# pianotiles.net
KiCad netlist of a schematic drawn in EAGLE
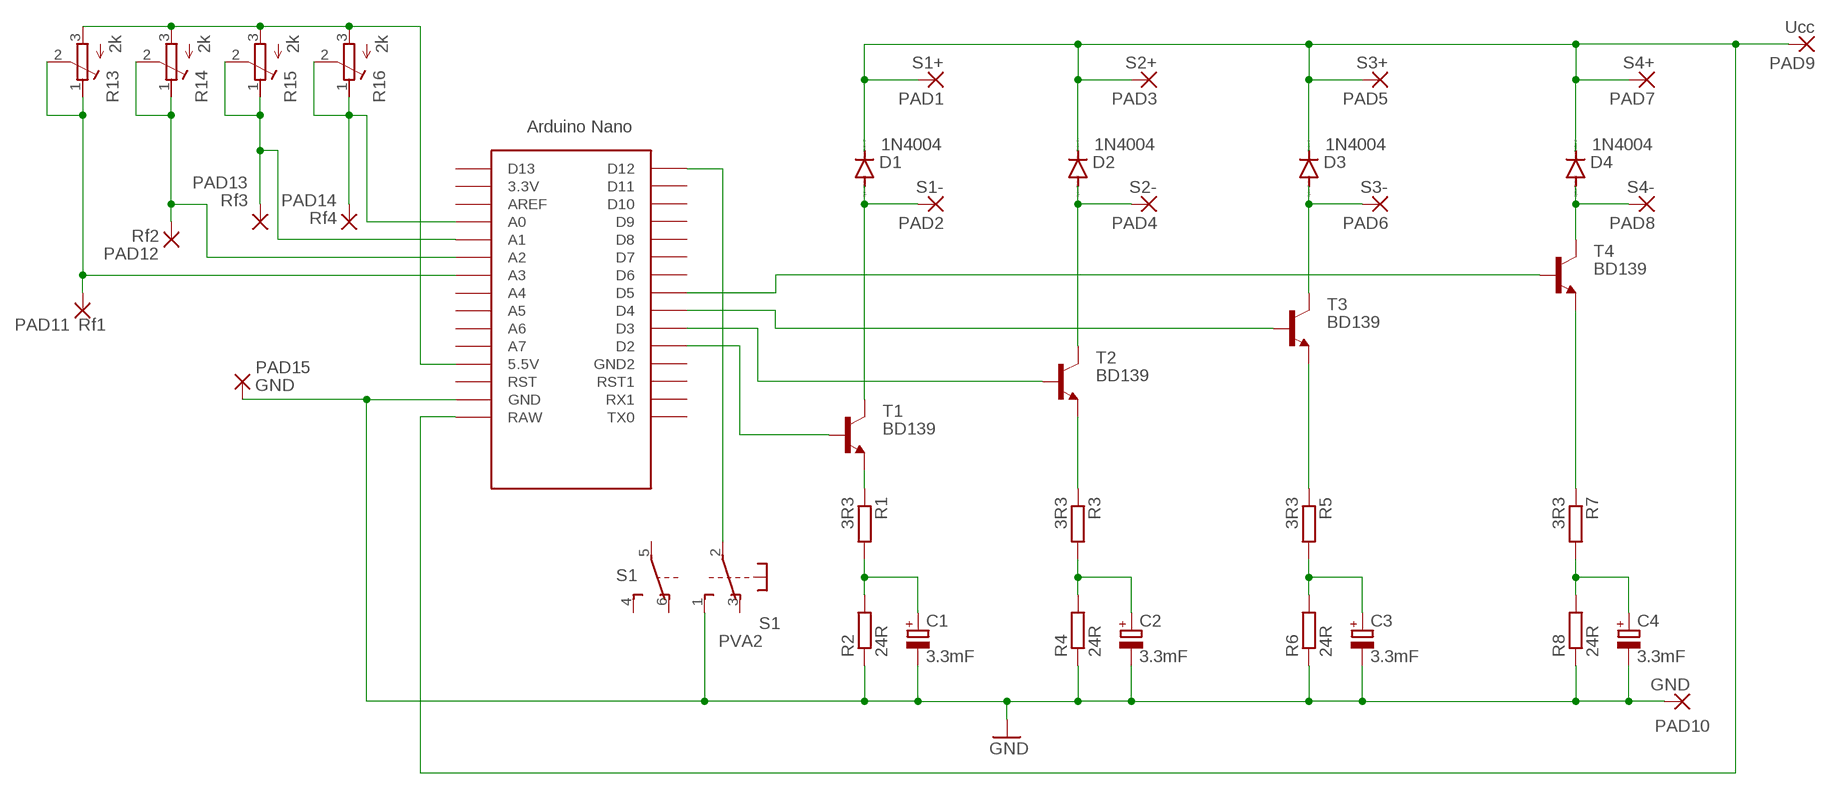
[diagram p0: schematic, sheet 1]

(export (version "E")
  (design (tool "Eeschema 10.0.6"))
  (components
    (comp (ref "C1")
      (value "3.3mF")
      (footprint "eagle-import:E5-10,5")
      (libsource (lib "eagle-import") (part "CPOL-EUE5-10.5"))
    )
    (comp (ref "C2")
      (value "3.3mF")
      (footprint "eagle-import:E5-10,5")
      (libsource (lib "eagle-import") (part "CPOL-EUE5-10.5"))
    )
    (comp (ref "C3")
      (value "3.3mF")
      (footprint "eagle-import:E5-10,5")
      (libsource (lib "eagle-import") (part "CPOL-EUE5-10.5"))
    )
    (comp (ref "C4")
      (value "3.3mF")
      (footprint "eagle-import:E5-10,5")
      (libsource (lib "eagle-import") (part "CPOL-EUE5-10.5"))
    )
    (comp (ref "D1")
      (value "1N4004")
      (footprint "eagle-import:DO41-10")
      (libsource (lib "eagle-import") (part "1N4004"))
    )
    (comp (ref "D2")
      (value "1N4004")
      (footprint "eagle-import:DO41-10")
      (libsource (lib "eagle-import") (part "1N4004"))
    )
    (comp (ref "D3")
      (value "1N4004")
      (footprint "eagle-import:DO41-10")
      (libsource (lib "eagle-import") (part "1N4004"))
    )
    (comp (ref "D4")
      (value "1N4004")
      (footprint "eagle-import:DO41-10")
      (libsource (lib "eagle-import") (part "1N4004"))
    )
    (comp (ref "PAD1")
      (value "S1+")
      (footprint "eagle-import:2,15_1,0")
      (libsource (lib "eagle-import") (part "2,15/1,0"))
    )
    (comp (ref "PAD2")
      (value "S1-")
      (footprint "eagle-import:2,15_1,0")
      (libsource (lib "eagle-import") (part "2,15/1,0"))
    )
    (comp (ref "PAD3")
      (value "S2+")
      (footprint "eagle-import:2,15_1,0")
      (libsource (lib "eagle-import") (part "2,15/1,0"))
    )
    (comp (ref "PAD4")
      (value "S2-")
      (footprint "eagle-import:2,15_1,0")
      (libsource (lib "eagle-import") (part "2,15/1,0"))
    )
    (comp (ref "PAD5")
      (value "S3+")
      (footprint "eagle-import:2,15_1,0")
      (libsource (lib "eagle-import") (part "2,15/1,0"))
    )
    (comp (ref "PAD6")
      (value "S3-")
      (footprint "eagle-import:2,15_1,0")
      (libsource (lib "eagle-import") (part "2,15/1,0"))
    )
    (comp (ref "PAD7")
      (value "S4+")
      (footprint "eagle-import:2,15_1,0")
      (libsource (lib "eagle-import") (part "2,15/1,0"))
    )
    (comp (ref "PAD8")
      (value "S4-")
      (footprint "eagle-import:2,15_1,0")
      (libsource (lib "eagle-import") (part "2,15/1,0"))
    )
    (comp (ref "PAD9")
      (value "Ucc")
      (footprint "eagle-import:2,54_1,0")
      (libsource (lib "eagle-import") (part "2,54/1,0"))
    )
    (comp (ref "PAD10")
      (value "GND")
      (footprint "eagle-import:2,54_1,0")
      (libsource (lib "eagle-import") (part "2,54/1,0"))
    )
    (comp (ref "PAD11")
      (value "Rf1")
      (footprint "eagle-import:2,15_1,0")
      (libsource (lib "eagle-import") (part "2,15/1,0"))
    )
    (comp (ref "PAD12")
      (value "Rf2")
      (footprint "eagle-import:2,15_1,0")
      (libsource (lib "eagle-import") (part "2,15/1,0"))
    )
    (comp (ref "PAD13")
      (value "Rf3")
      (footprint "eagle-import:2,15_1,0")
      (libsource (lib "eagle-import") (part "2,15/1,0"))
    )
    (comp (ref "PAD14")
      (value "Rf4")
      (footprint "eagle-import:2,15_1,0")
      (libsource (lib "eagle-import") (part "2,15/1,0"))
    )
    (comp (ref "PAD15")
      (value "GND")
      (footprint "eagle-import:2,15_1,0")
      (libsource (lib "eagle-import") (part "2,15/1,0"))
    )
    (comp (ref "R1")
      (value "3R3")
      (footprint "eagle-import:0309_10")
      (libsource (lib "eagle-import") (part "R-EU_0309/10"))
    )
    (comp (ref "R2")
      (value "24R")
      (footprint "eagle-import:0309_10")
      (libsource (lib "eagle-import") (part "R-EU_0309/10"))
    )
    (comp (ref "R3")
      (value "3R3")
      (footprint "eagle-import:0309_10")
      (libsource (lib "eagle-import") (part "R-EU_0309/10"))
    )
    (comp (ref "R4")
      (value "24R")
      (footprint "eagle-import:0309_10")
      (libsource (lib "eagle-import") (part "R-EU_0309/10"))
    )
    (comp (ref "R5")
      (value "3R3")
      (footprint "eagle-import:0309_10")
      (libsource (lib "eagle-import") (part "R-EU_0309/10"))
    )
    (comp (ref "R6")
      (value "24R")
      (footprint "eagle-import:0309_10")
      (libsource (lib "eagle-import") (part "R-EU_0309/10"))
    )
    (comp (ref "R7")
      (value "3R3")
      (footprint "eagle-import:0309_10")
      (libsource (lib "eagle-import") (part "R-EU_0309/10"))
    )
    (comp (ref "R8")
      (value "24R")
      (footprint "eagle-import:0309_10")
      (libsource (lib "eagle-import") (part "R-EU_0309/10"))
    )
    (comp (ref "R13")
      (value "2k")
      (footprint "eagle-import:RTRIMT93YA")
      (libsource (lib "eagle-import") (part "R-TRIMMT93YA"))
    )
    (comp (ref "R14")
      (value "2k")
      (footprint "eagle-import:RTRIMT93YA")
      (libsource (lib "eagle-import") (part "R-TRIMMT93YA"))
    )
    (comp (ref "R15")
      (value "2k")
      (footprint "eagle-import:RTRIMT93YA")
      (libsource (lib "eagle-import") (part "R-TRIMMT93YA"))
    )
    (comp (ref "R16")
      (value "2k")
      (footprint "eagle-import:RTRIMT93YA")
      (libsource (lib "eagle-import") (part "R-TRIMMT93YA"))
    )
    (comp (ref "S1")
      (value "PVA2")
      (footprint "eagle-import:PVA2F")
      (libsource (lib "eagle-import") (part "PVA2"))
    )
    (comp (ref "T1")
      (value "BD139")
      (footprint "eagle-import:TO126")
      (libsource (lib "eagle-import") (part "BD139"))
    )
    (comp (ref "T2")
      (value "BD139")
      (footprint "eagle-import:TO126")
      (libsource (lib "eagle-import") (part "BD139"))
    )
    (comp (ref "T3")
      (value "BD139")
      (footprint "eagle-import:TO126")
      (libsource (lib "eagle-import") (part "BD139"))
    )
    (comp (ref "T4")
      (value "BD139")
      (footprint "eagle-import:TO126")
      (libsource (lib "eagle-import") (part "BD139"))
    )
    (comp (ref "U$1")
      (value "NANO")
      (footprint "eagle-import:NANO")
      (libsource (lib "eagle-import") (part "NANO"))
    )
  )
  (nets
    (net (code "1") (name "GND") (class "Default")
      (node (ref "C1") (pin "-") (pinfunction "-_-") (pintype "passive"))
      (node (ref "C2") (pin "-") (pinfunction "-_-") (pintype "passive"))
      (node (ref "C3") (pin "-") (pinfunction "-_-") (pintype "passive"))
      (node (ref "C4") (pin "-") (pinfunction "-_-") (pintype "passive"))
      (node (ref "PAD10") (pin "1") (pinfunction "P_1") (pintype "passive"))
      (node (ref "PAD15") (pin "1") (pinfunction "P_1") (pintype "passive"))
      (node (ref "R2") (pin "1") (pinfunction "1_1") (pintype "passive"))
      (node (ref "R4") (pin "1") (pinfunction "1_1") (pintype "passive"))
      (node (ref "R6") (pin "1") (pinfunction "1_1") (pintype "passive"))
      (node (ref "R8") (pin "1") (pinfunction "1_1") (pintype "passive"))
      (node (ref "S1") (pin "1") (pinfunction "S_1") (pintype "passive"))
      (node (ref "U$1") (pin "GND") (pinfunction "GND_GND") (pintype "bidirectional"))
    )
    (net (code "2") (name "Net-(C1-Pad+)") (class "Default")
      (node (ref "C1") (pin "+") (pinfunction "+_+") (pintype "passive"))
      (node (ref "R1") (pin "2") (pinfunction "2_2") (pintype "passive"))
      (node (ref "R2") (pin "2") (pinfunction "2_2") (pintype "passive"))
    )
    (net (code "3") (name "Net-(C2-Pad+)") (class "Default")
      (node (ref "C2") (pin "+") (pinfunction "+_+") (pintype "passive"))
      (node (ref "R3") (pin "2") (pinfunction "2_2") (pintype "passive"))
      (node (ref "R4") (pin "2") (pinfunction "2_2") (pintype "passive"))
    )
    (net (code "4") (name "Net-(C3-Pad+)") (class "Default")
      (node (ref "C3") (pin "+") (pinfunction "+_+") (pintype "passive"))
      (node (ref "R5") (pin "2") (pinfunction "2_2") (pintype "passive"))
      (node (ref "R6") (pin "2") (pinfunction "2_2") (pintype "passive"))
    )
    (net (code "5") (name "Net-(C4-Pad+)") (class "Default")
      (node (ref "C4") (pin "+") (pinfunction "+_+") (pintype "passive"))
      (node (ref "R7") (pin "2") (pinfunction "2_2") (pintype "passive"))
      (node (ref "R8") (pin "2") (pinfunction "2_2") (pintype "passive"))
    )
    (net (code "6") (name "Net-(PAD1-P)") (class "Default")
      (node (ref "D1") (pin "C") (pinfunction "C_C") (pintype "passive"))
      (node (ref "D2") (pin "C") (pinfunction "C_C") (pintype "passive"))
      (node (ref "D3") (pin "C") (pinfunction "C_C") (pintype "passive"))
      (node (ref "D4") (pin "C") (pinfunction "C_C") (pintype "passive"))
      (node (ref "PAD1") (pin "1") (pinfunction "P_1") (pintype "passive"))
      (node (ref "PAD3") (pin "1") (pinfunction "P_1") (pintype "passive"))
      (node (ref "PAD5") (pin "1") (pinfunction "P_1") (pintype "passive"))
      (node (ref "PAD7") (pin "1") (pinfunction "P_1") (pintype "passive"))
      (node (ref "PAD9") (pin "1") (pinfunction "P_1") (pintype "passive"))
      (node (ref "U$1") (pin "RAW") (pinfunction "RAW_RAW") (pintype "bidirectional"))
    )
    (net (code "7") (name "Net-(PAD2-P)") (class "Default")
      (node (ref "D1") (pin "A") (pinfunction "A_A") (pintype "passive"))
      (node (ref "PAD2") (pin "1") (pinfunction "P_1") (pintype "passive"))
      (node (ref "T1") (pin "2") (pinfunction "C_2") (pintype "passive"))
    )
    (net (code "8") (name "Net-(PAD4-P)") (class "Default")
      (node (ref "D2") (pin "A") (pinfunction "A_A") (pintype "passive"))
      (node (ref "PAD4") (pin "1") (pinfunction "P_1") (pintype "passive"))
      (node (ref "T2") (pin "2") (pinfunction "C_2") (pintype "passive"))
    )
    (net (code "9") (name "Net-(PAD6-P)") (class "Default")
      (node (ref "D3") (pin "A") (pinfunction "A_A") (pintype "passive"))
      (node (ref "PAD6") (pin "1") (pinfunction "P_1") (pintype "passive"))
      (node (ref "T3") (pin "2") (pinfunction "C_2") (pintype "passive"))
    )
    (net (code "10") (name "Net-(PAD8-P)") (class "Default")
      (node (ref "D4") (pin "A") (pinfunction "A_A") (pintype "passive"))
      (node (ref "PAD8") (pin "1") (pinfunction "P_1") (pintype "passive"))
      (node (ref "T4") (pin "2") (pinfunction "C_2") (pintype "passive"))
    )
    (net (code "11") (name "Net-(PAD11-P)") (class "Default")
      (node (ref "PAD11") (pin "1") (pinfunction "P_1") (pintype "passive"))
      (node (ref "R13") (pin "1") (pinfunction "E_1") (pintype "passive"))
      (node (ref "R13") (pin "2") (pinfunction "S_2") (pintype "passive"))
      (node (ref "U$1") (pin "A3") (pinfunction "A3_A3") (pintype "bidirectional"))
    )
    (net (code "12") (name "Net-(PAD12-P)") (class "Default")
      (node (ref "PAD12") (pin "1") (pinfunction "P_1") (pintype "passive"))
      (node (ref "R14") (pin "1") (pinfunction "E_1") (pintype "passive"))
      (node (ref "R14") (pin "2") (pinfunction "S_2") (pintype "passive"))
      (node (ref "U$1") (pin "A2") (pinfunction "A2_A2") (pintype "bidirectional"))
    )
    (net (code "13") (name "Net-(PAD13-P)") (class "Default")
      (node (ref "PAD13") (pin "1") (pinfunction "P_1") (pintype "passive"))
      (node (ref "R15") (pin "1") (pinfunction "E_1") (pintype "passive"))
      (node (ref "R15") (pin "2") (pinfunction "S_2") (pintype "passive"))
      (node (ref "U$1") (pin "A1") (pinfunction "A1_A1") (pintype "bidirectional"))
    )
    (net (code "14") (name "Net-(PAD14-P)") (class "Default")
      (node (ref "PAD14") (pin "1") (pinfunction "P_1") (pintype "passive"))
      (node (ref "R16") (pin "1") (pinfunction "E_1") (pintype "passive"))
      (node (ref "R16") (pin "2") (pinfunction "S_2") (pintype "passive"))
      (node (ref "U$1") (pin "A0") (pinfunction "A0_A0") (pintype "bidirectional"))
    )
    (net (code "15") (name "Net-(R13-A)") (class "Default")
      (node (ref "R13") (pin "3") (pinfunction "A_3") (pintype "passive"))
      (node (ref "R14") (pin "3") (pinfunction "A_3") (pintype "passive"))
      (node (ref "R15") (pin "3") (pinfunction "A_3") (pintype "passive"))
      (node (ref "R16") (pin "3") (pinfunction "A_3") (pintype "passive"))
      (node (ref "U$1") (pin "5V") (pinfunction "5.5V_5V") (pintype "bidirectional"))
    )
    (net (code "16") (name "Net-(S1A-P)") (class "Default")
      (node (ref "S1") (pin "2") (pinfunction "P_2") (pintype "passive"))
      (node (ref "U$1") (pin "D12") (pinfunction "D12_D12") (pintype "bidirectional"))
    )
    (net (code "17") (name "Net-(T1-B)") (class "Default")
      (node (ref "T1") (pin "3") (pinfunction "B_3") (pintype "passive"))
      (node (ref "U$1") (pin "D2") (pinfunction "D2_D2") (pintype "bidirectional"))
    )
    (net (code "18") (name "Net-(T1-E)") (class "Default")
      (node (ref "R1") (pin "1") (pinfunction "1_1") (pintype "passive"))
      (node (ref "T1") (pin "1") (pinfunction "E_1") (pintype "passive"))
    )
    (net (code "19") (name "Net-(T2-B)") (class "Default")
      (node (ref "T2") (pin "3") (pinfunction "B_3") (pintype "passive"))
      (node (ref "U$1") (pin "D3") (pinfunction "D3_D3") (pintype "bidirectional"))
    )
    (net (code "20") (name "Net-(T2-E)") (class "Default")
      (node (ref "R3") (pin "1") (pinfunction "1_1") (pintype "passive"))
      (node (ref "T2") (pin "1") (pinfunction "E_1") (pintype "passive"))
    )
    (net (code "21") (name "Net-(T3-B)") (class "Default")
      (node (ref "T3") (pin "3") (pinfunction "B_3") (pintype "passive"))
      (node (ref "U$1") (pin "D4") (pinfunction "D4_D4") (pintype "bidirectional"))
    )
    (net (code "22") (name "Net-(T3-E)") (class "Default")
      (node (ref "R5") (pin "1") (pinfunction "1_1") (pintype "passive"))
      (node (ref "T3") (pin "1") (pinfunction "E_1") (pintype "passive"))
    )
    (net (code "23") (name "Net-(T4-B)") (class "Default")
      (node (ref "T4") (pin "3") (pinfunction "B_3") (pintype "passive"))
      (node (ref "U$1") (pin "D5") (pinfunction "D5_D5") (pintype "bidirectional"))
    )
    (net (code "24") (name "Net-(T4-E)") (class "Default")
      (node (ref "R7") (pin "1") (pinfunction "1_1") (pintype "passive"))
      (node (ref "T4") (pin "1") (pinfunction "E_1") (pintype "passive"))
    )
    (net (code "25") (name "unconnected-(S1A-O-Pad3)") (class "Default")
      (node (ref "S1") (pin "3") (pinfunction "O_3") (pintype "passive"))
    )
    (net (code "26") (name "unconnected-(S1B-O-Pad6)") (class "Default")
      (node (ref "S1") (pin "6") (pinfunction "O_6") (pintype "passive"))
    )
    (net (code "27") (name "unconnected-(S1B-P-Pad5)") (class "Default")
      (node (ref "S1") (pin "5") (pinfunction "P_5") (pintype "passive"))
    )
    (net (code "28") (name "unconnected-(S1B-S-Pad4)") (class "Default")
      (node (ref "S1") (pin "4") (pinfunction "S_4") (pintype "passive"))
    )
    (net (code "29") (name "unconnected-(U$1-GND2-PadGND1)") (class "Default")
      (node (ref "U$1") (pin "GND1") (pinfunction "GND2_GND1") (pintype "bidirectional"))
    )
    (net (code "30") (name "unconnected-(U$1-Pad3.3V)") (class "Default")
      (node (ref "U$1") (pin "3.3V") (pinfunction "3.3V_3.3V") (pintype "bidirectional"))
    )
    (net (code "31") (name "unconnected-(U$1-PadA4)") (class "Default")
      (node (ref "U$1") (pin "A4") (pinfunction "A4_A4") (pintype "bidirectional"))
    )
    (net (code "32") (name "unconnected-(U$1-PadA5)") (class "Default")
      (node (ref "U$1") (pin "A5") (pinfunction "A5_A5") (pintype "bidirectional"))
    )
    (net (code "33") (name "unconnected-(U$1-PadA6)") (class "Default")
      (node (ref "U$1") (pin "A6") (pinfunction "A6_A6") (pintype "bidirectional"))
    )
    (net (code "34") (name "unconnected-(U$1-PadA7)") (class "Default")
      (node (ref "U$1") (pin "A7") (pinfunction "A7_A7") (pintype "bidirectional"))
    )
    (net (code "35") (name "unconnected-(U$1-PadAREF)") (class "Default")
      (node (ref "U$1") (pin "AREF") (pinfunction "AREF_AREF") (pintype "bidirectional"))
    )
    (net (code "36") (name "unconnected-(U$1-PadD6)") (class "Default")
      (node (ref "U$1") (pin "D6") (pinfunction "D6_D6") (pintype "bidirectional"))
    )
    (net (code "37") (name "unconnected-(U$1-PadD7)") (class "Default")
      (node (ref "U$1") (pin "D7") (pinfunction "D7_D7") (pintype "bidirectional"))
    )
    (net (code "38") (name "unconnected-(U$1-PadD8)") (class "Default")
      (node (ref "U$1") (pin "D8") (pinfunction "D8_D8") (pintype "bidirectional"))
    )
    (net (code "39") (name "unconnected-(U$1-PadD9)") (class "Default")
      (node (ref "U$1") (pin "D9") (pinfunction "D9_D9") (pintype "bidirectional"))
    )
    (net (code "40") (name "unconnected-(U$1-PadD10)") (class "Default")
      (node (ref "U$1") (pin "D10") (pinfunction "D10_D10") (pintype "bidirectional"))
    )
    (net (code "41") (name "unconnected-(U$1-PadD11)") (class "Default")
      (node (ref "U$1") (pin "D11") (pinfunction "D11_D11") (pintype "bidirectional"))
    )
    (net (code "42") (name "unconnected-(U$1-PadD13)") (class "Default")
      (node (ref "U$1") (pin "D13") (pinfunction "D13_D13") (pintype "bidirectional"))
    )
    (net (code "43") (name "unconnected-(U$1-PadICSP1)") (class "Default")
      (node (ref "U$1") (pin "ICSP1") (pinfunction "ICSP1_ICSP1") (pintype "bidirectional"))
    )
    (net (code "44") (name "unconnected-(U$1-PadICSP2)") (class "Default")
      (node (ref "U$1") (pin "ICSP2") (pinfunction "ICSP2_ICSP2") (pintype "bidirectional"))
    )
    (net (code "45") (name "unconnected-(U$1-PadICSP3)") (class "Default")
      (node (ref "U$1") (pin "ICSP3") (pinfunction "ICSP3_ICSP3") (pintype "bidirectional"))
    )
    (net (code "46") (name "unconnected-(U$1-PadICSP4)") (class "Default")
      (node (ref "U$1") (pin "ICSP4") (pinfunction "ICSP4_ICSP4") (pintype "bidirectional"))
    )
    (net (code "47") (name "unconnected-(U$1-PadICSP5)") (class "Default")
      (node (ref "U$1") (pin "ICSP5") (pinfunction "ICSP5_ICSP5") (pintype "bidirectional"))
    )
    (net (code "48") (name "unconnected-(U$1-PadICSP6)") (class "Default")
      (node (ref "U$1") (pin "ICSP6") (pinfunction "ICSP6_ICSP6") (pintype "bidirectional"))
    )
    (net (code "49") (name "unconnected-(U$1-PadRST)") (class "Default")
      (node (ref "U$1") (pin "RST") (pinfunction "RST_RST") (pintype "bidirectional"))
    )
    (net (code "50") (name "unconnected-(U$1-PadRST1)") (class "Default")
      (node (ref "U$1") (pin "RST1") (pinfunction "RST1_RST1") (pintype "bidirectional"))
    )
    (net (code "51") (name "unconnected-(U$1-PadRX1)") (class "Default")
      (node (ref "U$1") (pin "RX1") (pinfunction "RX1_RX1") (pintype "bidirectional"))
    )
    (net (code "52") (name "unconnected-(U$1-PadTX0)") (class "Default")
      (node (ref "U$1") (pin "TX0") (pinfunction "TX0_TX0") (pintype "bidirectional"))
    )
  )
)
